# schematic.net
KiCad netlist of a schematic drawn in EasyEDA
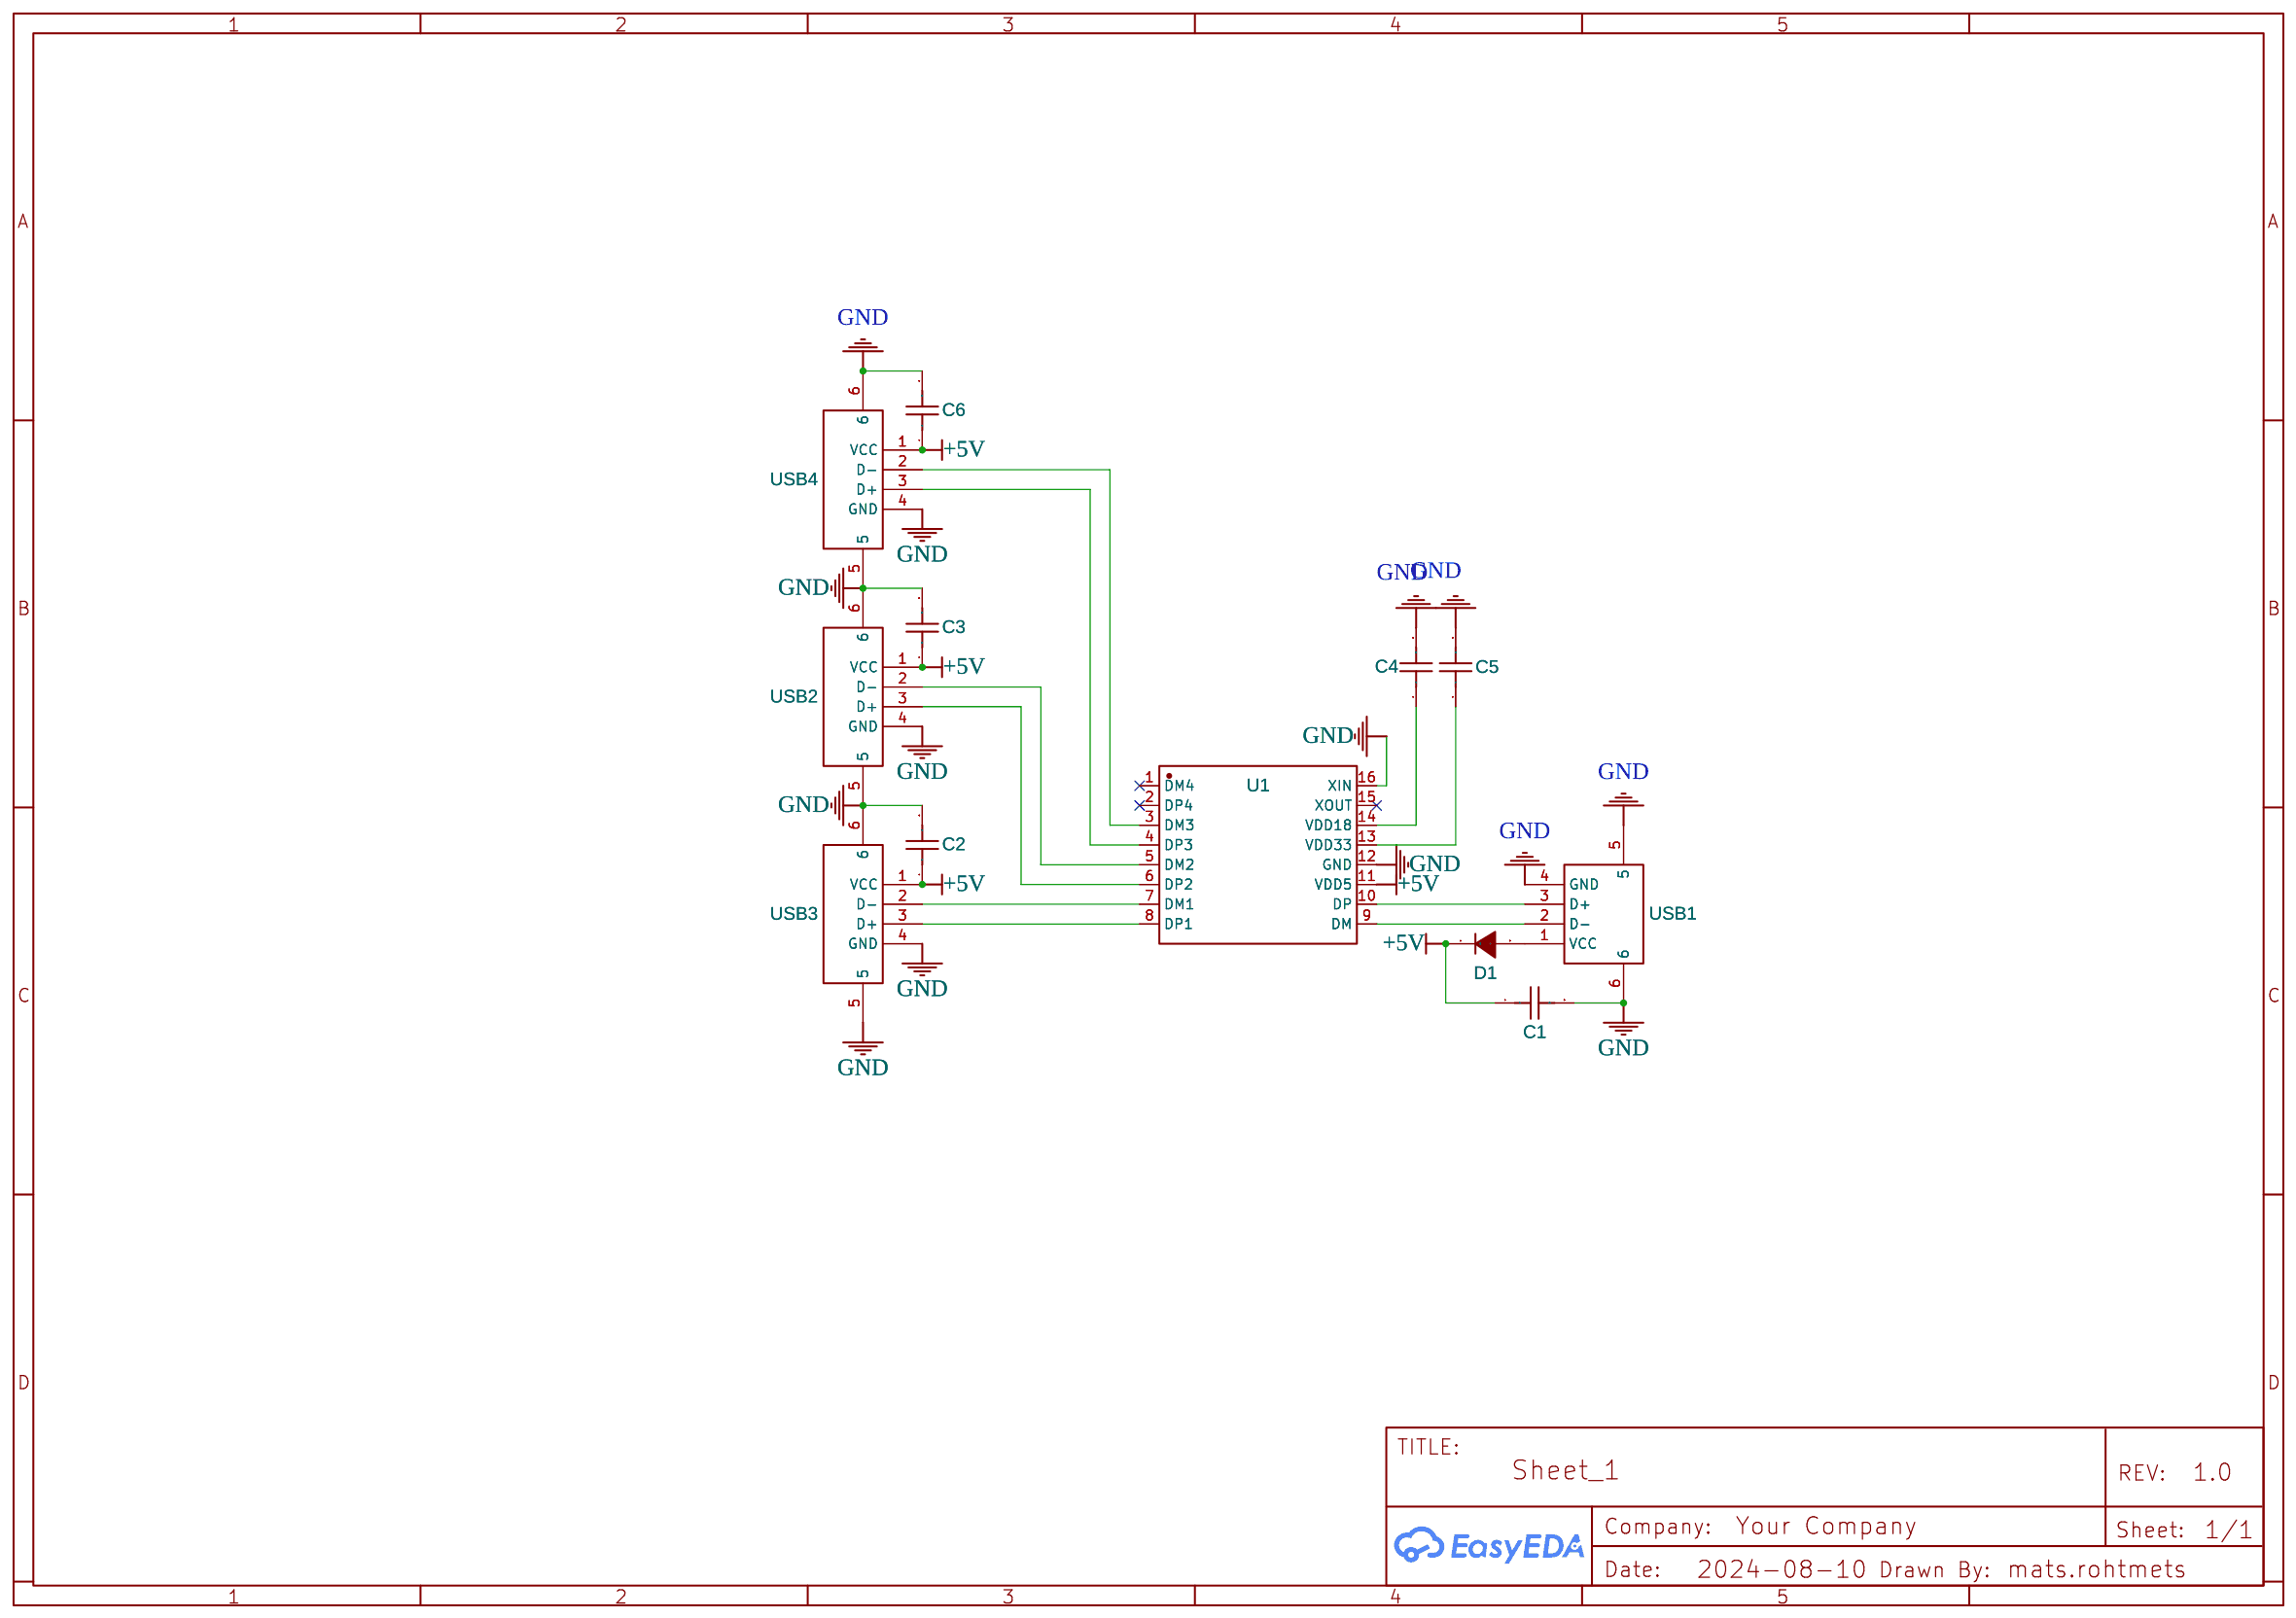
[diagram p0: schematic sheet]

(export (version "E")
  (design (tool "Eeschema 10.0.6"))
  (components
    (comp (ref "C1")
      (value "10uF")
      (fields
        (field (name "Manufacturer Part") "CL10A106KP8NNNC")
        (field (name "Manufacturer") "SAMSUNG(三星)")
      )
      (libsource (lib "") (part "CL10A106KP8NNNC_1"))
    )
    (comp (ref "C2")
      (value "10uF")
      (fields
        (field (name "Manufacturer Part") "CL10A106KP8NNNC")
        (field (name "Manufacturer") "SAMSUNG(三星)")
      )
      (libsource (lib "") (part "CL10A106KP8NNNC"))
    )
    (comp (ref "C3")
      (value "10uF")
      (fields
        (field (name "Manufacturer Part") "CL10A106KP8NNNC")
        (field (name "Manufacturer") "SAMSUNG(三星)")
      )
      (libsource (lib "") (part "CL10A106KP8NNNC"))
    )
    (comp (ref "C4")
      (value "10uF")
      (fields
        (field (name "Manufacturer Part") "CL10A106KP8NNNC")
        (field (name "Manufacturer") "SAMSUNG(三星)")
      )
      (libsource (lib "") (part "CL10A106KP8NNNC"))
    )
    (comp (ref "C5")
      (value "10uF")
      (fields
        (field (name "Manufacturer Part") "CL10A106KP8NNNC")
        (field (name "Manufacturer") "SAMSUNG(三星)")
      )
      (libsource (lib "") (part "CL10A106KP8NNNC"))
    )
    (comp (ref "C6")
      (value "10uF")
      (fields
        (field (name "Manufacturer Part") "CL10A106KP8NNNC")
        (field (name "Manufacturer") "SAMSUNG(三星)")
      )
      (libsource (lib "") (part "CL10A106KP8NNNC"))
    )
    (comp (ref "D1")
      (value "NSR0320MW2T1G")
      (fields (field (name "Manufacturer") "onsemi(安森美)"))
      (libsource (lib "") (part "NSR0320MW2T1G"))
    )
    (comp (ref "U1")
      (value "SL2.1A")
      (fields (field (name "Manufacturer") "CoreChips(和芯润德)"))
      (libsource (lib "") (part "SL2.1A"))
    )
    (comp (ref "USB1")
      (value "U-G-04DD-W-01")
      (fields (field (name "Manufacturer Part") "U-G-O4DD-W-1") (field (name "Manufacturer") "韩国韩荣"))
      (libsource (lib "") (part "U-G-04DD-W-01"))
    )
    (comp (ref "USB2")
      (value "USB-AF-90-14.4X13.6-H7.0-DIP")
      (fields (field (name "Manufacturer Part") "903-131A1011D10100") (field (name "Manufacturer") "精拓金"))
      (libsource (lib "") (part "USB-AF-90-14.4X13.6-H7.0-DIP"))
    )
    (comp (ref "USB3")
      (value "USB-AF-90-14.4X13.6-H7.0-DIP")
      (fields (field (name "Manufacturer Part") "903-131A1011D10100") (field (name "Manufacturer") "精拓金"))
      (libsource (lib "") (part "USB-AF-90-14.4X13.6-H7.0-DIP"))
    )
    (comp (ref "USB4")
      (value "USB-AF-90-14.4X13.6-H7.0-DIP")
      (fields (field (name "Manufacturer Part") "903-131A1011D10100") (field (name "Manufacturer") "精拓金"))
      (libsource (lib "") (part "USB-AF-90-14.4X13.6-H7.0-DIP"))
    )
  )
  (nets
    (net (code "1") (name "+5V") (class "Default")
      (node (ref "C1") (pin "1") (pinfunction "1_1") (pintype "unspecified"))
      (node (ref "C2") (pin "1") (pinfunction "1_1") (pintype "unspecified"))
      (node (ref "C3") (pin "1") (pinfunction "1_1") (pintype "unspecified"))
      (node (ref "C6") (pin "1") (pinfunction "1_1") (pintype "unspecified"))
      (node (ref "D1") (pin "1") (pinfunction "C_1") (pintype "unspecified"))
      (node (ref "U1") (pin "11") (pinfunction "VDD5_11") (pintype "unspecified"))
      (node (ref "USB2") (pin "1") (pinfunction "VCC_1") (pintype "unspecified"))
      (node (ref "USB3") (pin "1") (pinfunction "VCC_1") (pintype "unspecified"))
      (node (ref "USB4") (pin "1") (pinfunction "VCC_1") (pintype "unspecified"))
    )
    (net (code "2") (name "GND") (class "Default")
      (node (ref "C1") (pin "2") (pinfunction "2_2") (pintype "unspecified"))
      (node (ref "C2") (pin "2") (pinfunction "2_2") (pintype "unspecified"))
      (node (ref "C3") (pin "2") (pinfunction "2_2") (pintype "unspecified"))
      (node (ref "C4") (pin "2") (pinfunction "2_2") (pintype "unspecified"))
      (node (ref "C5") (pin "2") (pinfunction "2_2") (pintype "unspecified"))
      (node (ref "C6") (pin "2") (pinfunction "2_2") (pintype "unspecified"))
      (node (ref "U1") (pin "12") (pinfunction "GND_12") (pintype "unspecified"))
      (node (ref "U1") (pin "16") (pinfunction "XIN_16") (pintype "unspecified"))
      (node (ref "USB1") (pin "4") (pinfunction "GND_4") (pintype "unspecified"))
      (node (ref "USB1") (pin "5") (pinfunction "5_5") (pintype "unspecified"))
      (node (ref "USB1") (pin "6") (pinfunction "6_6") (pintype "unspecified"))
      (node (ref "USB2") (pin "4") (pinfunction "GND_4") (pintype "unspecified"))
      (node (ref "USB2") (pin "5") (pinfunction "5_5") (pintype "unspecified"))
      (node (ref "USB2") (pin "6") (pinfunction "6_6") (pintype "unspecified"))
      (node (ref "USB3") (pin "4") (pinfunction "GND_4") (pintype "unspecified"))
      (node (ref "USB3") (pin "5") (pinfunction "5_5") (pintype "unspecified"))
      (node (ref "USB3") (pin "6") (pinfunction "6_6") (pintype "unspecified"))
      (node (ref "USB4") (pin "4") (pinfunction "GND_4") (pintype "unspecified"))
      (node (ref "USB4") (pin "5") (pinfunction "5_5") (pintype "unspecified"))
      (node (ref "USB4") (pin "6") (pinfunction "6_6") (pintype "unspecified"))
    )
    (net (code "3") (name "Net-(D1-A)") (class "Default")
      (node (ref "D1") (pin "2") (pinfunction "A_2") (pintype "unspecified"))
      (node (ref "USB1") (pin "1") (pinfunction "VCC_1") (pintype "unspecified"))
    )
    (net (code "4") (name "Net-(U1-DM)") (class "Default")
      (node (ref "U1") (pin "9") (pinfunction "DM_9") (pintype "unspecified"))
      (node (ref "USB1") (pin "2") (pinfunction "D-_2") (pintype "unspecified"))
    )
    (net (code "5") (name "Net-(U1-DM1)") (class "Default")
      (node (ref "U1") (pin "7") (pinfunction "DM1_7") (pintype "unspecified"))
      (node (ref "USB3") (pin "2") (pinfunction "D-_2") (pintype "unspecified"))
    )
    (net (code "6") (name "Net-(U1-DM2)") (class "Default")
      (node (ref "U1") (pin "5") (pinfunction "DM2_5") (pintype "unspecified"))
      (node (ref "USB2") (pin "2") (pinfunction "D-_2") (pintype "unspecified"))
    )
    (net (code "7") (name "Net-(U1-DM3)") (class "Default")
      (node (ref "U1") (pin "3") (pinfunction "DM3_3") (pintype "unspecified"))
      (node (ref "USB4") (pin "2") (pinfunction "D-_2") (pintype "unspecified"))
    )
    (net (code "8") (name "Net-(U1-DP)") (class "Default")
      (node (ref "U1") (pin "10") (pinfunction "DP_10") (pintype "unspecified"))
      (node (ref "USB1") (pin "3") (pinfunction "D+_3") (pintype "unspecified"))
    )
    (net (code "9") (name "Net-(U1-DP1)") (class "Default")
      (node (ref "U1") (pin "8") (pinfunction "DP1_8") (pintype "unspecified"))
      (node (ref "USB3") (pin "3") (pinfunction "D+_3") (pintype "unspecified"))
    )
    (net (code "10") (name "Net-(U1-DP2)") (class "Default")
      (node (ref "U1") (pin "6") (pinfunction "DP2_6") (pintype "unspecified"))
      (node (ref "USB2") (pin "3") (pinfunction "D+_3") (pintype "unspecified"))
    )
    (net (code "11") (name "Net-(U1-DP3)") (class "Default")
      (node (ref "U1") (pin "4") (pinfunction "DP3_4") (pintype "unspecified"))
      (node (ref "USB4") (pin "3") (pinfunction "D+_3") (pintype "unspecified"))
    )
    (net (code "12") (name "Net-(U1-VDD18)") (class "Default")
      (node (ref "C4") (pin "1") (pinfunction "1_1") (pintype "unspecified"))
      (node (ref "U1") (pin "14") (pinfunction "VDD18_14") (pintype "unspecified"))
    )
    (net (code "13") (name "Net-(U1-VDD33)") (class "Default")
      (node (ref "C5") (pin "1") (pinfunction "1_1") (pintype "unspecified"))
      (node (ref "U1") (pin "13") (pinfunction "VDD33_13") (pintype "unspecified"))
    )
    (net (code "14") (name "unconnected-(U1-DM4-Pad1)") (class "Default")
      (node (ref "U1") (pin "1") (pinfunction "DM4_1") (pintype "unspecified+no_connect"))
    )
    (net (code "15") (name "unconnected-(U1-DP4-Pad2)") (class "Default")
      (node (ref "U1") (pin "2") (pinfunction "DP4_2") (pintype "unspecified+no_connect"))
    )
    (net (code "16") (name "unconnected-(U1-XOUT-Pad15)") (class "Default")
      (node (ref "U1") (pin "15") (pinfunction "XOUT_15") (pintype "unspecified+no_connect"))
    )
  )
)
